# RawWaves_rev1-0.net
KiCad netlist of a schematic drawn in EAGLE
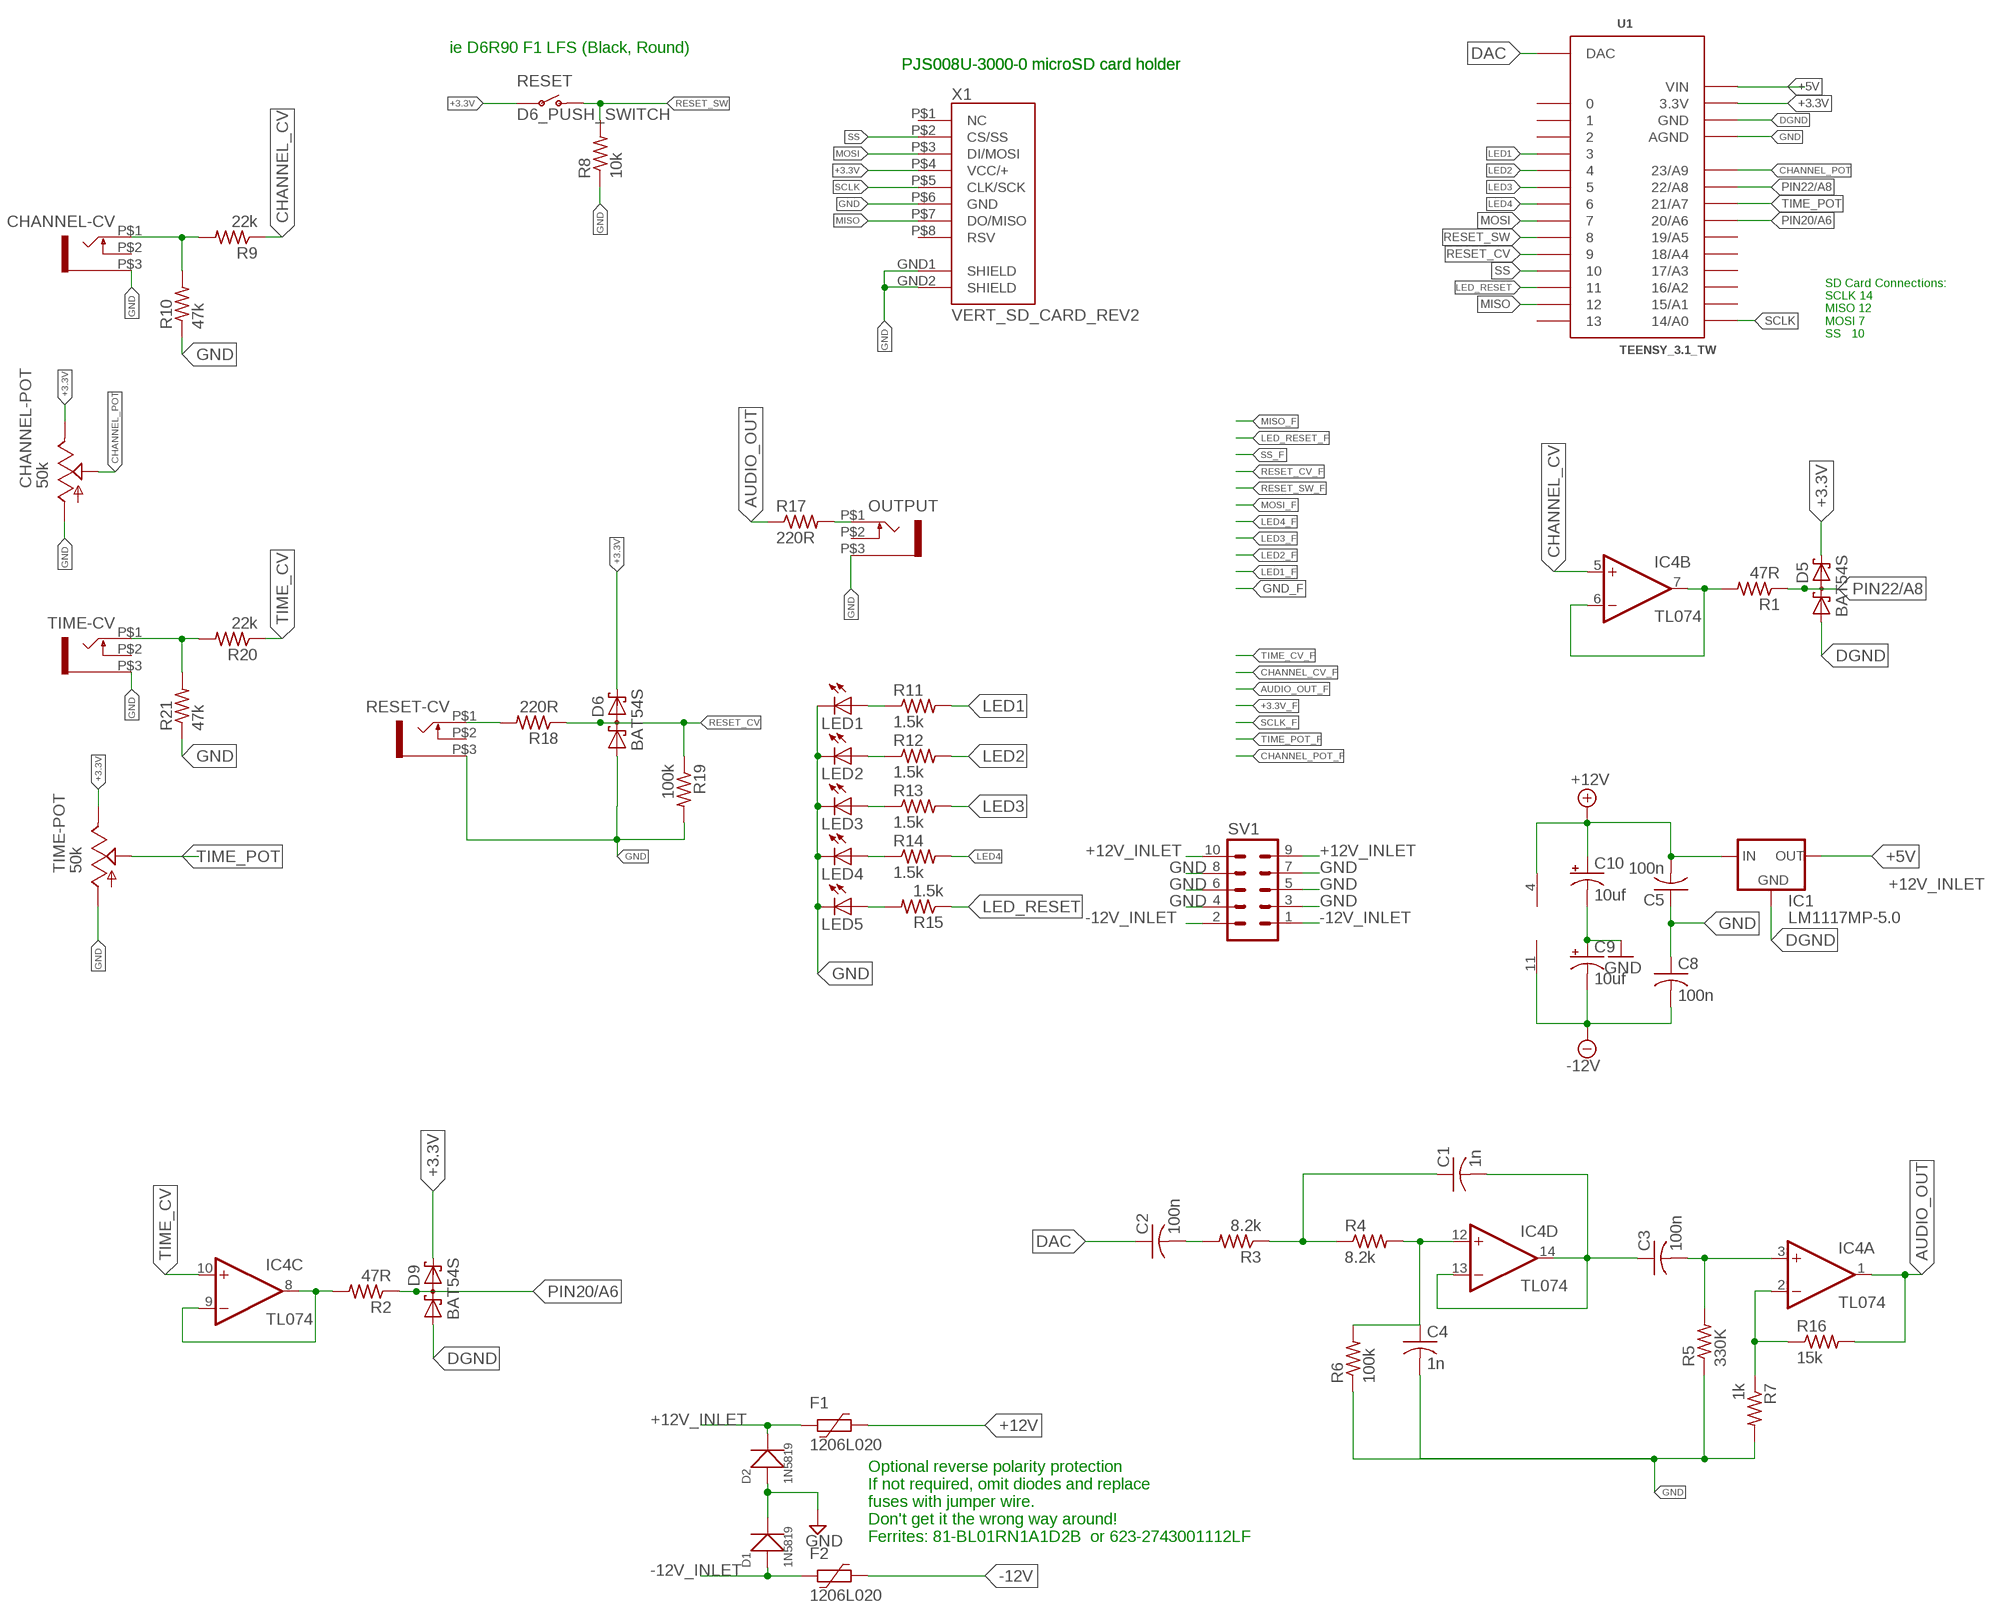
[diagram p0: schematic, sheet 1]

(export (version "E")
  (design (tool "Eeschema 10.0.6"))
  (components
    (comp (ref "C1")
      (value "1n")
      (footprint "eagle-import:C0805")
      (libsource (lib "eagle-import") (part "C-USC0805"))
    )
    (comp (ref "C2")
      (value "100n")
      (footprint "eagle-import:C0805")
      (libsource (lib "eagle-import") (part "C-USC0805"))
    )
    (comp (ref "C3")
      (value "100n")
      (footprint "eagle-import:C0805")
      (libsource (lib "eagle-import") (part "C-USC0805"))
    )
    (comp (ref "C4")
      (value "1n")
      (footprint "eagle-import:C0805")
      (libsource (lib "eagle-import") (part "C-USC0805"))
    )
    (comp (ref "C5")
      (value "100n")
      (footprint "eagle-import:C0805")
      (libsource (lib "eagle-import") (part "C-USC0805"))
    )
    (comp (ref "C8")
      (value "100n")
      (footprint "eagle-import:C0805")
      (libsource (lib "eagle-import") (part "C-USC0805"))
    )
    (comp (ref "C9")
      (value "10uf")
      (footprint "eagle-import:PANASONIC_B")
      (libsource (lib "eagle-import") (part "CPOL-USB"))
    )
    (comp (ref "C10")
      (value "10uf")
      (footprint "eagle-import:PANASONIC_B")
      (libsource (lib "eagle-import") (part "CPOL-USB"))
    )
    (comp (ref "CHANNEL-CV")
      (value "WQP-PJ301M-12_JACK")
      (footprint "eagle-import:WQP-PJ301M-12_JACK")
      (libsource (lib "eagle-import") (part "WQP-PJ301M-12_JACK"))
    )
    (comp (ref "CHANNEL-POT")
      (value "50k")
      (footprint "eagle-import:EVUF")
      (libsource (lib "eagle-import") (part "ALPHA-9MMAF2"))
    )
    (comp (ref "D1")
      (value "1N5819")
      (footprint "eagle-import:SOD-123")
      (fields (field (name "MPN") "B0540W"))
      (libsource (lib "eagle-import") (part "SMD-DIODE-SCHOTTKY-40V-500MA(SOD-123)"))
    )
    (comp (ref "D2")
      (value "1N5819")
      (footprint "eagle-import:SOD-123")
      (fields (field (name "MPN") "B0540W"))
      (libsource (lib "eagle-import") (part "SMD-DIODE-SCHOTTKY-40V-500MA(SOD-123)"))
    )
    (comp (ref "D5")
      (value "BAT54S")
      (footprint "eagle-import:SOT23")
      (libsource (lib "eagle-import") (part "BAT54S"))
    )
    (comp (ref "D6")
      (value "BAT54S")
      (footprint "eagle-import:SOT23")
      (libsource (lib "eagle-import") (part "BAT54S"))
    )
    (comp (ref "D9")
      (value "BAT54S")
      (footprint "eagle-import:SOT23")
      (libsource (lib "eagle-import") (part "BAT54S"))
    )
    (comp (ref "F1")
      (value "1206L020")
      (footprint "eagle-import:1206L")
      (fields (field (name "MF") "Littelfuse"))
      (libsource (lib "eagle-import") (part "?1206L020"))
    )
    (comp (ref "F2")
      (value "1206L020")
      (footprint "eagle-import:1206L")
      (fields (field (name "MF") "Littelfuse"))
      (libsource (lib "eagle-import") (part "?1206L020"))
    )
    (comp (ref "IC1")
      (value "LM1117MP-5.0")
      (footprint "eagle-import:SOT223")
      (fields (field (name "MF") "Texas Instruments"))
      (libsource (lib "eagle-import") (part "LM1117?-MP5.0"))
    )
    (comp (ref "IC4")
      (value "TL074")
      (footprint "eagle-import:SO14")
      (libsource (lib "eagle-import") (part "TL074D"))
    )
    (comp (ref "LED1")
      (value "LED3MM")
      (footprint "eagle-import:LED3MM")
      (libsource (lib "eagle-import") (part "LED3MM"))
    )
    (comp (ref "LED2")
      (value "LED3MM")
      (footprint "eagle-import:LED3MM")
      (libsource (lib "eagle-import") (part "LED3MM"))
    )
    (comp (ref "LED3")
      (value "LED3MM")
      (footprint "eagle-import:LED3MM")
      (libsource (lib "eagle-import") (part "LED3MM"))
    )
    (comp (ref "LED4")
      (value "LED3MM")
      (footprint "eagle-import:LED3MM")
      (libsource (lib "eagle-import") (part "LED3MM"))
    )
    (comp (ref "LED5")
      (value "LED3MM")
      (footprint "eagle-import:LED3MM")
      (libsource (lib "eagle-import") (part "LED3MM"))
    )
    (comp (ref "OUTPUT")
      (value "WQP-PJ301M-12_JACK")
      (footprint "eagle-import:WQP-PJ301M-12_JACK")
      (libsource (lib "eagle-import") (part "WQP-PJ301M-12_JACK"))
    )
    (comp (ref "R1")
      (value "47R")
      (footprint "eagle-import:R0805")
      (libsource (lib "eagle-import") (part "R-US_R0805"))
    )
    (comp (ref "R2")
      (value "47R")
      (footprint "eagle-import:R0805")
      (libsource (lib "eagle-import") (part "R-US_R0805"))
    )
    (comp (ref "R3")
      (value "8.2k")
      (footprint "eagle-import:R0805")
      (libsource (lib "eagle-import") (part "R-US_R0805"))
    )
    (comp (ref "R4")
      (value "8.2k")
      (footprint "eagle-import:R0805")
      (libsource (lib "eagle-import") (part "R-US_R0805"))
    )
    (comp (ref "R5")
      (value "330K")
      (footprint "eagle-import:R0805")
      (libsource (lib "eagle-import") (part "R-US_R0805"))
    )
    (comp (ref "R6")
      (value "100k")
      (footprint "eagle-import:R0805")
      (libsource (lib "eagle-import") (part "R-US_R0805"))
    )
    (comp (ref "R7")
      (value "1k")
      (footprint "eagle-import:R0805")
      (libsource (lib "eagle-import") (part "R-US_R0805"))
    )
    (comp (ref "R8")
      (value "10k")
      (footprint "eagle-import:R0805")
      (libsource (lib "eagle-import") (part "R-US_R0805"))
    )
    (comp (ref "R9")
      (value "22k")
      (footprint "eagle-import:R0805")
      (libsource (lib "eagle-import") (part "R-US_R0805"))
    )
    (comp (ref "R10")
      (value "47k")
      (footprint "eagle-import:R0805")
      (libsource (lib "eagle-import") (part "R-US_R0805"))
    )
    (comp (ref "R11")
      (value "1.5k")
      (footprint "eagle-import:R0805")
      (libsource (lib "eagle-import") (part "R-US_R0805"))
    )
    (comp (ref "R12")
      (value "1.5k")
      (footprint "eagle-import:R0805")
      (libsource (lib "eagle-import") (part "R-US_R0805"))
    )
    (comp (ref "R13")
      (value "1.5k")
      (footprint "eagle-import:R0805")
      (libsource (lib "eagle-import") (part "R-US_R0805"))
    )
    (comp (ref "R14")
      (value "1.5k")
      (footprint "eagle-import:R0805")
      (libsource (lib "eagle-import") (part "R-US_R0805"))
    )
    (comp (ref "R15")
      (value "1.5k")
      (footprint "eagle-import:R0805")
      (libsource (lib "eagle-import") (part "R-US_R0805"))
    )
    (comp (ref "R16")
      (value "15k")
      (footprint "eagle-import:R0805")
      (libsource (lib "eagle-import") (part "R-US_R0805"))
    )
    (comp (ref "R17")
      (value "220R")
      (footprint "eagle-import:R0805")
      (libsource (lib "eagle-import") (part "R-US_R0805"))
    )
    (comp (ref "R18")
      (value "220R")
      (footprint "eagle-import:R0805")
      (libsource (lib "eagle-import") (part "R-US_R0805"))
    )
    (comp (ref "R19")
      (value "100k")
      (footprint "eagle-import:R0805")
      (libsource (lib "eagle-import") (part "R-US_R0805"))
    )
    (comp (ref "R20")
      (value "22k")
      (footprint "eagle-import:R0805")
      (libsource (lib "eagle-import") (part "R-US_R0805"))
    )
    (comp (ref "R21")
      (value "47k")
      (footprint "eagle-import:R0805")
      (libsource (lib "eagle-import") (part "R-US_R0805"))
    )
    (comp (ref "RESET")
      (value "D6_PUSH_SWITCH")
      (footprint "eagle-import:D6_BUTTON_RND")
      (libsource (lib "eagle-import") (part "D6_PUSH_SWITCH"))
    )
    (comp (ref "RESET-CV")
      (value "WQP-PJ301M-12_JACK")
      (footprint "eagle-import:WQP-PJ301M-12_JACK")
      (libsource (lib "eagle-import") (part "WQP-PJ301M-12_JACK"))
    )
    (comp (ref "SV1")
      (value "10_PIN_HEADER")
      (footprint "eagle-import:MA05-2")
      (libsource (lib "eagle-import") (part "10_PIN_HEADER"))
    )
    (comp (ref "TIME-CV")
      (value "WQP-PJ301M-12_JACK")
      (footprint "eagle-import:WQP-PJ301M-12_JACK")
      (libsource (lib "eagle-import") (part "WQP-PJ301M-12_JACK"))
    )
    (comp (ref "TIME-POT")
      (value "50k")
      (footprint "eagle-import:EVUF")
      (libsource (lib "eagle-import") (part "ALPHA-9MMAF2"))
    )
    (comp (ref "U1")
      (value "TEENSY_3.1_TW")
      (footprint "eagle-import:TEENSY_3.1_TW")
      (libsource (lib "eagle-import") (part "TEENSY_3.1_TW"))
    )
    (comp (ref "X1")
      (value "VERT_SD_CARD_REV2")
      (footprint "eagle-import:VERT_MICROSD_REV2")
      (libsource (lib "eagle-import") (part "VERT_SD_CARD_REV2"))
    )
  )
  (nets
    (net (code "1") (name "+3.3V") (class "Default")
      (node (ref "CHANNEL-POT") (pin "3") (pinfunction "E_3") (pintype "passive"))
      (node (ref "D5") (pin "2") (pinfunction "C2_2") (pintype "passive"))
      (node (ref "D6") (pin "2") (pinfunction "C2_2") (pintype "passive"))
      (node (ref "D9") (pin "2") (pinfunction "C2_2") (pintype "passive"))
      (node (ref "RESET") (pin "P$3") (pinfunction "P_P$3") (pintype "passive"))
      (node (ref "RESET") (pin "P$4") (pinfunction "P_P$4") (pintype "passive"))
      (node (ref "TIME-POT") (pin "3") (pinfunction "E_3") (pintype "passive"))
      (node (ref "U1") (pin "3.3V") (pinfunction "3.3V_3.3V") (pintype "power_in"))
      (node (ref "X1") (pin "P$4") (pinfunction "VCC/+_P$4") (pintype "bidirectional"))
    )
    (net (code "3") (name "+5V") (class "Default")
      (node (ref "IC1") (pin "2") (pinfunction "OUT_2") (pintype "passive"))
      (node (ref "IC1") (pin "4") (pinfunction "OUT_4") (pintype "passive"))
      (node (ref "U1") (pin "VIN") (pinfunction "VIN_VIN") (pintype "power_in"))
    )
    (net (code "4") (name "+12V") (class "Default")
      (node (ref "C10") (pin "+") (pinfunction "+_+") (pintype "passive"))
      (node (ref "C5") (pin "2") (pinfunction "2_2") (pintype "passive"))
      (node (ref "F1") (pin "1") (pinfunction "1_1") (pintype "passive"))
      (node (ref "IC1") (pin "3") (pinfunction "IN_3") (pintype "input"))
      (node (ref "IC4") (pin "4") (pinfunction "V+_4") (pintype "power_in"))
    )
    (net (code "5") (name "-12V") (class "Default")
      (node (ref "C8") (pin "2") (pinfunction "2_2") (pintype "passive"))
      (node (ref "C9") (pin "-") (pinfunction "-_-") (pintype "passive"))
      (node (ref "F2") (pin "1") (pinfunction "1_1") (pintype "passive"))
      (node (ref "IC4") (pin "11") (pinfunction "V-_11") (pintype "power_in"))
    )
    (net (code "6") (name "/+12V_INLET") (class "Default")
      (node (ref "D2") (pin "-") (pinfunction "-_-") (pintype "passive"))
      (node (ref "F1") (pin "2") (pinfunction "2_2") (pintype "passive"))
      (node (ref "SV1") (pin "10") (pinfunction "10_10") (pintype "passive"))
      (node (ref "SV1") (pin "9") (pinfunction "9_9") (pintype "passive"))
    )
    (net (code "7") (name "/-12V_INLET") (class "Default")
      (node (ref "D1") (pin "+") (pinfunction "+_+") (pintype "passive"))
      (node (ref "F2") (pin "2") (pinfunction "2_2") (pintype "passive"))
      (node (ref "SV1") (pin "1") (pinfunction "1_1") (pintype "passive"))
      (node (ref "SV1") (pin "2") (pinfunction "2_2") (pintype "passive"))
    )
    (net (code "8") (name "AUDIO_OUT") (class "Default")
      (node (ref "IC4") (pin "1") (pinfunction "OUT_1") (pintype "output"))
      (node (ref "R16") (pin "2") (pinfunction "2_2") (pintype "passive"))
      (node (ref "R17") (pin "1") (pinfunction "1_1") (pintype "passive"))
    )
    (net (code "10") (name "CHANNEL_CV") (class "Default")
      (node (ref "IC4") (pin "5") (pinfunction "+IN_5") (pintype "input"))
      (node (ref "R9") (pin "1") (pinfunction "1_1") (pintype "passive"))
    )
    (net (code "12") (name "CHANNEL_POT") (class "Default")
      (node (ref "CHANNEL-POT") (pin "2") (pinfunction "S_2") (pintype "passive"))
      (node (ref "U1") (pin "23/A9") (pinfunction "23/A9_23/A9") (pintype "bidirectional"))
    )
    (net (code "14") (name "DAC") (class "Default")
      (node (ref "C2") (pin "1") (pinfunction "1_1") (pintype "passive"))
      (node (ref "U1") (pin "DAC") (pinfunction "DAC_DAC") (pintype "bidirectional"))
    )
    (net (code "15") (name "DGND") (class "Default")
      (node (ref "D5") (pin "1") (pinfunction "A1_1") (pintype "passive"))
      (node (ref "D9") (pin "1") (pinfunction "A1_1") (pintype "passive"))
      (node (ref "IC1") (pin "1") (pinfunction "GND_1") (pintype "input"))
      (node (ref "U1") (pin "GND") (pinfunction "GND_GND") (pintype "power_in"))
    )
    (net (code "16") (name "GND") (class "Default")
      (node (ref "C10") (pin "-") (pinfunction "-_-") (pintype "passive"))
      (node (ref "C4") (pin "2") (pinfunction "2_2") (pintype "passive"))
      (node (ref "C5") (pin "1") (pinfunction "1_1") (pintype "passive"))
      (node (ref "C8") (pin "1") (pinfunction "1_1") (pintype "passive"))
      (node (ref "C9") (pin "+") (pinfunction "+_+") (pintype "passive"))
      (node (ref "CHANNEL-CV") (pin "P$3") (pinfunction "1_P$3") (pintype "passive"))
      (node (ref "CHANNEL-POT") (pin "1") (pinfunction "A_1") (pintype "passive"))
      (node (ref "D1") (pin "-") (pinfunction "-_-") (pintype "passive"))
      (node (ref "D2") (pin "+") (pinfunction "+_+") (pintype "passive"))
      (node (ref "D6") (pin "1") (pinfunction "A1_1") (pintype "passive"))
      (node (ref "LED1") (pin "K") (pinfunction "C_K") (pintype "passive"))
      (node (ref "LED2") (pin "K") (pinfunction "C_K") (pintype "passive"))
      (node (ref "LED3") (pin "K") (pinfunction "C_K") (pintype "passive"))
      (node (ref "LED4") (pin "K") (pinfunction "C_K") (pintype "passive"))
      (node (ref "LED5") (pin "K") (pinfunction "C_K") (pintype "passive"))
      (node (ref "OUTPUT") (pin "P$3") (pinfunction "1_P$3") (pintype "passive"))
      (node (ref "R10") (pin "1") (pinfunction "1_1") (pintype "passive"))
      (node (ref "R19") (pin "2") (pinfunction "2_2") (pintype "passive"))
      (node (ref "R21") (pin "1") (pinfunction "1_1") (pintype "passive"))
      (node (ref "R5") (pin "1") (pinfunction "1_1") (pintype "passive"))
      (node (ref "R6") (pin "1") (pinfunction "1_1") (pintype "passive"))
      (node (ref "R7") (pin "2") (pinfunction "2_2") (pintype "passive"))
      (node (ref "R8") (pin "1") (pinfunction "1_1") (pintype "passive"))
      (node (ref "RESET-CV") (pin "P$3") (pinfunction "1_P$3") (pintype "passive"))
      (node (ref "SV1") (pin "3") (pinfunction "3_3") (pintype "passive"))
      (node (ref "SV1") (pin "4") (pinfunction "4_4") (pintype "passive"))
      (node (ref "SV1") (pin "5") (pinfunction "5_5") (pintype "passive"))
      (node (ref "SV1") (pin "6") (pinfunction "6_6") (pintype "passive"))
      (node (ref "SV1") (pin "7") (pinfunction "7_7") (pintype "passive"))
      (node (ref "SV1") (pin "8") (pinfunction "8_8") (pintype "passive"))
      (node (ref "TIME-CV") (pin "P$3") (pinfunction "1_P$3") (pintype "passive"))
      (node (ref "TIME-POT") (pin "1") (pinfunction "A_1") (pintype "passive"))
      (node (ref "U1") (pin "AGND") (pinfunction "AGND_AGND") (pintype "power_in"))
      (node (ref "X1") (pin "GND1") (pinfunction "SHIELD_GND1") (pintype "bidirectional"))
      (node (ref "X1") (pin "GND2") (pinfunction "SHIELD_GND2") (pintype "bidirectional"))
      (node (ref "X1") (pin "P$6") (pinfunction "GND_P$6") (pintype "bidirectional"))
    )
    (net (code "18") (name "LED1") (class "Default")
      (node (ref "R11") (pin "2") (pinfunction "2_2") (pintype "passive"))
      (node (ref "U1") (pin "3") (pinfunction "3_3") (pintype "bidirectional"))
    )
    (net (code "20") (name "LED2") (class "Default")
      (node (ref "R12") (pin "2") (pinfunction "2_2") (pintype "passive"))
      (node (ref "U1") (pin "4") (pinfunction "4_4") (pintype "bidirectional"))
    )
    (net (code "22") (name "LED3") (class "Default")
      (node (ref "R13") (pin "2") (pinfunction "2_2") (pintype "passive"))
      (node (ref "U1") (pin "5") (pinfunction "5_5") (pintype "bidirectional"))
    )
    (net (code "24") (name "LED4") (class "Default")
      (node (ref "R14") (pin "2") (pinfunction "2_2") (pintype "passive"))
      (node (ref "U1") (pin "6") (pinfunction "6_6") (pintype "bidirectional"))
    )
    (net (code "26") (name "LED_RESET") (class "Default")
      (node (ref "R15") (pin "1") (pinfunction "1_1") (pintype "passive"))
      (node (ref "U1") (pin "11") (pinfunction "11_11") (pintype "bidirectional"))
    )
    (net (code "28") (name "MISO") (class "Default")
      (node (ref "U1") (pin "12") (pinfunction "12_12") (pintype "bidirectional"))
      (node (ref "X1") (pin "P$7") (pinfunction "DO/MISO_P$7") (pintype "bidirectional"))
    )
    (net (code "30") (name "MOSI") (class "Default")
      (node (ref "U1") (pin "7") (pinfunction "7_7") (pintype "bidirectional"))
      (node (ref "X1") (pin "P$3") (pinfunction "DI/MOSI_P$3") (pintype "bidirectional"))
    )
    (net (code "32") (name "Net-(C1-Pad1)") (class "Default")
      (node (ref "C1") (pin "1") (pinfunction "1_1") (pintype "passive"))
      (node (ref "R3") (pin "1") (pinfunction "1_1") (pintype "passive"))
      (node (ref "R4") (pin "1") (pinfunction "1_1") (pintype "passive"))
    )
    (net (code "33") (name "Net-(C2-Pad2)") (class "Default")
      (node (ref "C2") (pin "2") (pinfunction "2_2") (pintype "passive"))
      (node (ref "R3") (pin "2") (pinfunction "2_2") (pintype "passive"))
    )
    (net (code "34") (name "Net-(CHANNEL-CV-2)") (class "Default")
      (node (ref "CHANNEL-CV") (pin "P$1") (pinfunction "2_P$1") (pintype "passive"))
      (node (ref "R10") (pin "2") (pinfunction "2_2") (pintype "passive"))
      (node (ref "R9") (pin "2") (pinfunction "2_2") (pintype "passive"))
    )
    (net (code "35") (name "Net-(IC4A-+IN)") (class "Default")
      (node (ref "C3") (pin "2") (pinfunction "2_2") (pintype "passive"))
      (node (ref "IC4") (pin "3") (pinfunction "+IN_3") (pintype "input"))
      (node (ref "R5") (pin "2") (pinfunction "2_2") (pintype "passive"))
    )
    (net (code "36") (name "Net-(IC4A--IN)") (class "Default")
      (node (ref "IC4") (pin "2") (pinfunction "-IN_2") (pintype "input"))
      (node (ref "R16") (pin "1") (pinfunction "1_1") (pintype "passive"))
      (node (ref "R7") (pin "1") (pinfunction "1_1") (pintype "passive"))
    )
    (net (code "37") (name "Net-(IC4B--IN)") (class "Default")
      (node (ref "IC4") (pin "6") (pinfunction "-IN_6") (pintype "input"))
      (node (ref "IC4") (pin "7") (pinfunction "OUT_7") (pintype "output"))
      (node (ref "R1") (pin "2") (pinfunction "2_2") (pintype "passive"))
    )
    (net (code "38") (name "Net-(IC4C--IN)") (class "Default")
      (node (ref "IC4") (pin "8") (pinfunction "OUT_8") (pintype "output"))
      (node (ref "IC4") (pin "9") (pinfunction "-IN_9") (pintype "input"))
      (node (ref "R2") (pin "2") (pinfunction "2_2") (pintype "passive"))
    )
    (net (code "39") (name "Net-(IC4D-+IN)") (class "Default")
      (node (ref "C4") (pin "1") (pinfunction "1_1") (pintype "passive"))
      (node (ref "IC4") (pin "12") (pinfunction "+IN_12") (pintype "input"))
      (node (ref "R4") (pin "2") (pinfunction "2_2") (pintype "passive"))
      (node (ref "R6") (pin "2") (pinfunction "2_2") (pintype "passive"))
    )
    (net (code "40") (name "Net-(IC4D--IN)") (class "Default")
      (node (ref "C1") (pin "2") (pinfunction "2_2") (pintype "passive"))
      (node (ref "C3") (pin "1") (pinfunction "1_1") (pintype "passive"))
      (node (ref "IC4") (pin "13") (pinfunction "-IN_13") (pintype "input"))
      (node (ref "IC4") (pin "14") (pinfunction "OUT_14") (pintype "output"))
    )
    (net (code "41") (name "Net-(LED1-PadA)") (class "Default")
      (node (ref "LED1") (pin "A") (pinfunction "A_A") (pintype "passive"))
      (node (ref "R11") (pin "1") (pinfunction "1_1") (pintype "passive"))
    )
    (net (code "42") (name "Net-(LED2-PadA)") (class "Default")
      (node (ref "LED2") (pin "A") (pinfunction "A_A") (pintype "passive"))
      (node (ref "R12") (pin "1") (pinfunction "1_1") (pintype "passive"))
    )
    (net (code "43") (name "Net-(LED3-PadA)") (class "Default")
      (node (ref "LED3") (pin "A") (pinfunction "A_A") (pintype "passive"))
      (node (ref "R13") (pin "1") (pinfunction "1_1") (pintype "passive"))
    )
    (net (code "44") (name "Net-(LED4-PadA)") (class "Default")
      (node (ref "LED4") (pin "A") (pinfunction "A_A") (pintype "passive"))
      (node (ref "R14") (pin "1") (pinfunction "1_1") (pintype "passive"))
    )
    (net (code "45") (name "Net-(LED5-PadA)") (class "Default")
      (node (ref "LED5") (pin "A") (pinfunction "A_A") (pintype "passive"))
      (node (ref "R15") (pin "2") (pinfunction "2_2") (pintype "passive"))
    )
    (net (code "46") (name "Net-(OUTPUT-2)") (class "Default")
      (node (ref "OUTPUT") (pin "P$1") (pinfunction "2_P$1") (pintype "passive"))
      (node (ref "R17") (pin "2") (pinfunction "2_2") (pintype "passive"))
    )
    (net (code "47") (name "Net-(RESET-CV-2)") (class "Default")
      (node (ref "R18") (pin "2") (pinfunction "2_2") (pintype "passive"))
      (node (ref "RESET-CV") (pin "P$1") (pinfunction "2_P$1") (pintype "passive"))
    )
    (net (code "48") (name "Net-(TIME-CV-2)") (class "Default")
      (node (ref "R20") (pin "2") (pinfunction "2_2") (pintype "passive"))
      (node (ref "R21") (pin "2") (pinfunction "2_2") (pintype "passive"))
      (node (ref "TIME-CV") (pin "P$1") (pinfunction "2_P$1") (pintype "passive"))
    )
    (net (code "49") (name "PIN20{slash}A6") (class "Default")
      (node (ref "D9") (pin "3") (pinfunction "C1A2_3") (pintype "passive"))
      (node (ref "R2") (pin "1") (pinfunction "1_1") (pintype "passive"))
      (node (ref "U1") (pin "20/A6") (pinfunction "20/A6_20/A6") (pintype "bidirectional"))
    )
    (net (code "50") (name "PIN22{slash}A8") (class "Default")
      (node (ref "D5") (pin "3") (pinfunction "C1A2_3") (pintype "passive"))
      (node (ref "R1") (pin "1") (pinfunction "1_1") (pintype "passive"))
      (node (ref "U1") (pin "22/A8") (pinfunction "22/A8_22/A8") (pintype "bidirectional"))
    )
    (net (code "51") (name "RESET_CV") (class "Default")
      (node (ref "D6") (pin "3") (pinfunction "C1A2_3") (pintype "passive"))
      (node (ref "R18") (pin "1") (pinfunction "1_1") (pintype "passive"))
      (node (ref "R19") (pin "1") (pinfunction "1_1") (pintype "passive"))
      (node (ref "U1") (pin "9") (pinfunction "9_9") (pintype "bidirectional"))
    )
    (net (code "53") (name "RESET_SW") (class "Default")
      (node (ref "R8") (pin "2") (pinfunction "2_2") (pintype "passive"))
      (node (ref "RESET") (pin "P$1") (pinfunction "O_P$1") (pintype "passive"))
      (node (ref "RESET") (pin "P$2") (pinfunction "O_P$2") (pintype "passive"))
      (node (ref "U1") (pin "8") (pinfunction "8_8") (pintype "bidirectional"))
    )
    (net (code "55") (name "SCLK") (class "Default")
      (node (ref "U1") (pin "14/A0") (pinfunction "14/A0_14/A0") (pintype "bidirectional"))
      (node (ref "X1") (pin "P$5") (pinfunction "CLK/SCK_P$5") (pintype "bidirectional"))
    )
    (net (code "57") (name "SS") (class "Default")
      (node (ref "U1") (pin "10") (pinfunction "10_10") (pintype "bidirectional"))
      (node (ref "X1") (pin "P$2") (pinfunction "CS/SS_P$2") (pintype "bidirectional"))
    )
    (net (code "59") (name "TIME_CV") (class "Default")
      (node (ref "IC4") (pin "10") (pinfunction "+IN_10") (pintype "input"))
      (node (ref "R20") (pin "1") (pinfunction "1_1") (pintype "passive"))
    )
    (net (code "61") (name "TIME_POT") (class "Default")
      (node (ref "TIME-POT") (pin "2") (pinfunction "S_2") (pintype "passive"))
      (node (ref "U1") (pin "21/A7") (pinfunction "21/A7_21/A7") (pintype "bidirectional"))
    )
    (net (code "63") (name "unconnected-(CHANNEL-CV-3-PadP$2)") (class "Default")
      (node (ref "CHANNEL-CV") (pin "P$2") (pinfunction "3_P$2") (pintype "passive"))
    )
    (net (code "64") (name "unconnected-(OUTPUT-3-PadP$2)") (class "Default")
      (node (ref "OUTPUT") (pin "P$2") (pinfunction "3_P$2") (pintype "passive"))
    )
    (net (code "65") (name "unconnected-(RESET-CV-3-PadP$2)") (class "Default")
      (node (ref "RESET-CV") (pin "P$2") (pinfunction "3_P$2") (pintype "passive"))
    )
    (net (code "66") (name "unconnected-(TIME-CV-3-PadP$2)") (class "Default")
      (node (ref "TIME-CV") (pin "P$2") (pinfunction "3_P$2") (pintype "passive"))
    )
    (net (code "67") (name "unconnected-(U1-Pad0)") (class "Default")
      (node (ref "U1") (pin "0") (pinfunction "0_0") (pintype "bidirectional"))
    )
    (net (code "68") (name "unconnected-(U1-Pad1)") (class "Default")
      (node (ref "U1") (pin "1") (pinfunction "1_1") (pintype "bidirectional"))
    )
    (net (code "69") (name "unconnected-(U1-Pad2)") (class "Default")
      (node (ref "U1") (pin "2") (pinfunction "2_2") (pintype "bidirectional"))
    )
    (net (code "70") (name "unconnected-(U1-Pad13)") (class "Default")
      (node (ref "U1") (pin "13") (pinfunction "13_13") (pintype "bidirectional"))
    )
    (net (code "71") (name "unconnected-(U1-Pad15{slash}A1)") (class "Default")
      (node (ref "U1") (pin "15/A1") (pinfunction "15/A1_15/A1") (pintype "bidirectional"))
    )
    (net (code "72") (name "unconnected-(U1-Pad16{slash}A2)") (class "Default")
      (node (ref "U1") (pin "16/A2") (pinfunction "16/A2_16/A2") (pintype "bidirectional"))
    )
    (net (code "73") (name "unconnected-(U1-Pad17{slash}A3)") (class "Default")
      (node (ref "U1") (pin "17/A3") (pinfunction "17/A3_17/A3") (pintype "bidirectional"))
    )
    (net (code "74") (name "unconnected-(U1-Pad18{slash}A4)") (class "Default")
      (node (ref "U1") (pin "18/A4") (pinfunction "18/A4_18/A4") (pintype "bidirectional"))
    )
    (net (code "75") (name "unconnected-(U1-Pad19{slash}A5)") (class "Default")
      (node (ref "U1") (pin "19/A5") (pinfunction "19/A5_19/A5") (pintype "bidirectional"))
    )
    (net (code "76") (name "unconnected-(X1-NC-PadP$1)") (class "Default")
      (node (ref "X1") (pin "P$1") (pinfunction "NC_P$1") (pintype "bidirectional"))
    )
    (net (code "77") (name "unconnected-(X1-RSV-PadP$8)") (class "Default")
      (node (ref "X1") (pin "P$8") (pinfunction "RSV_P$8") (pintype "bidirectional"))
    )
  )
)
